# main.net
KiCad netlist of a schematic drawn in EAGLE
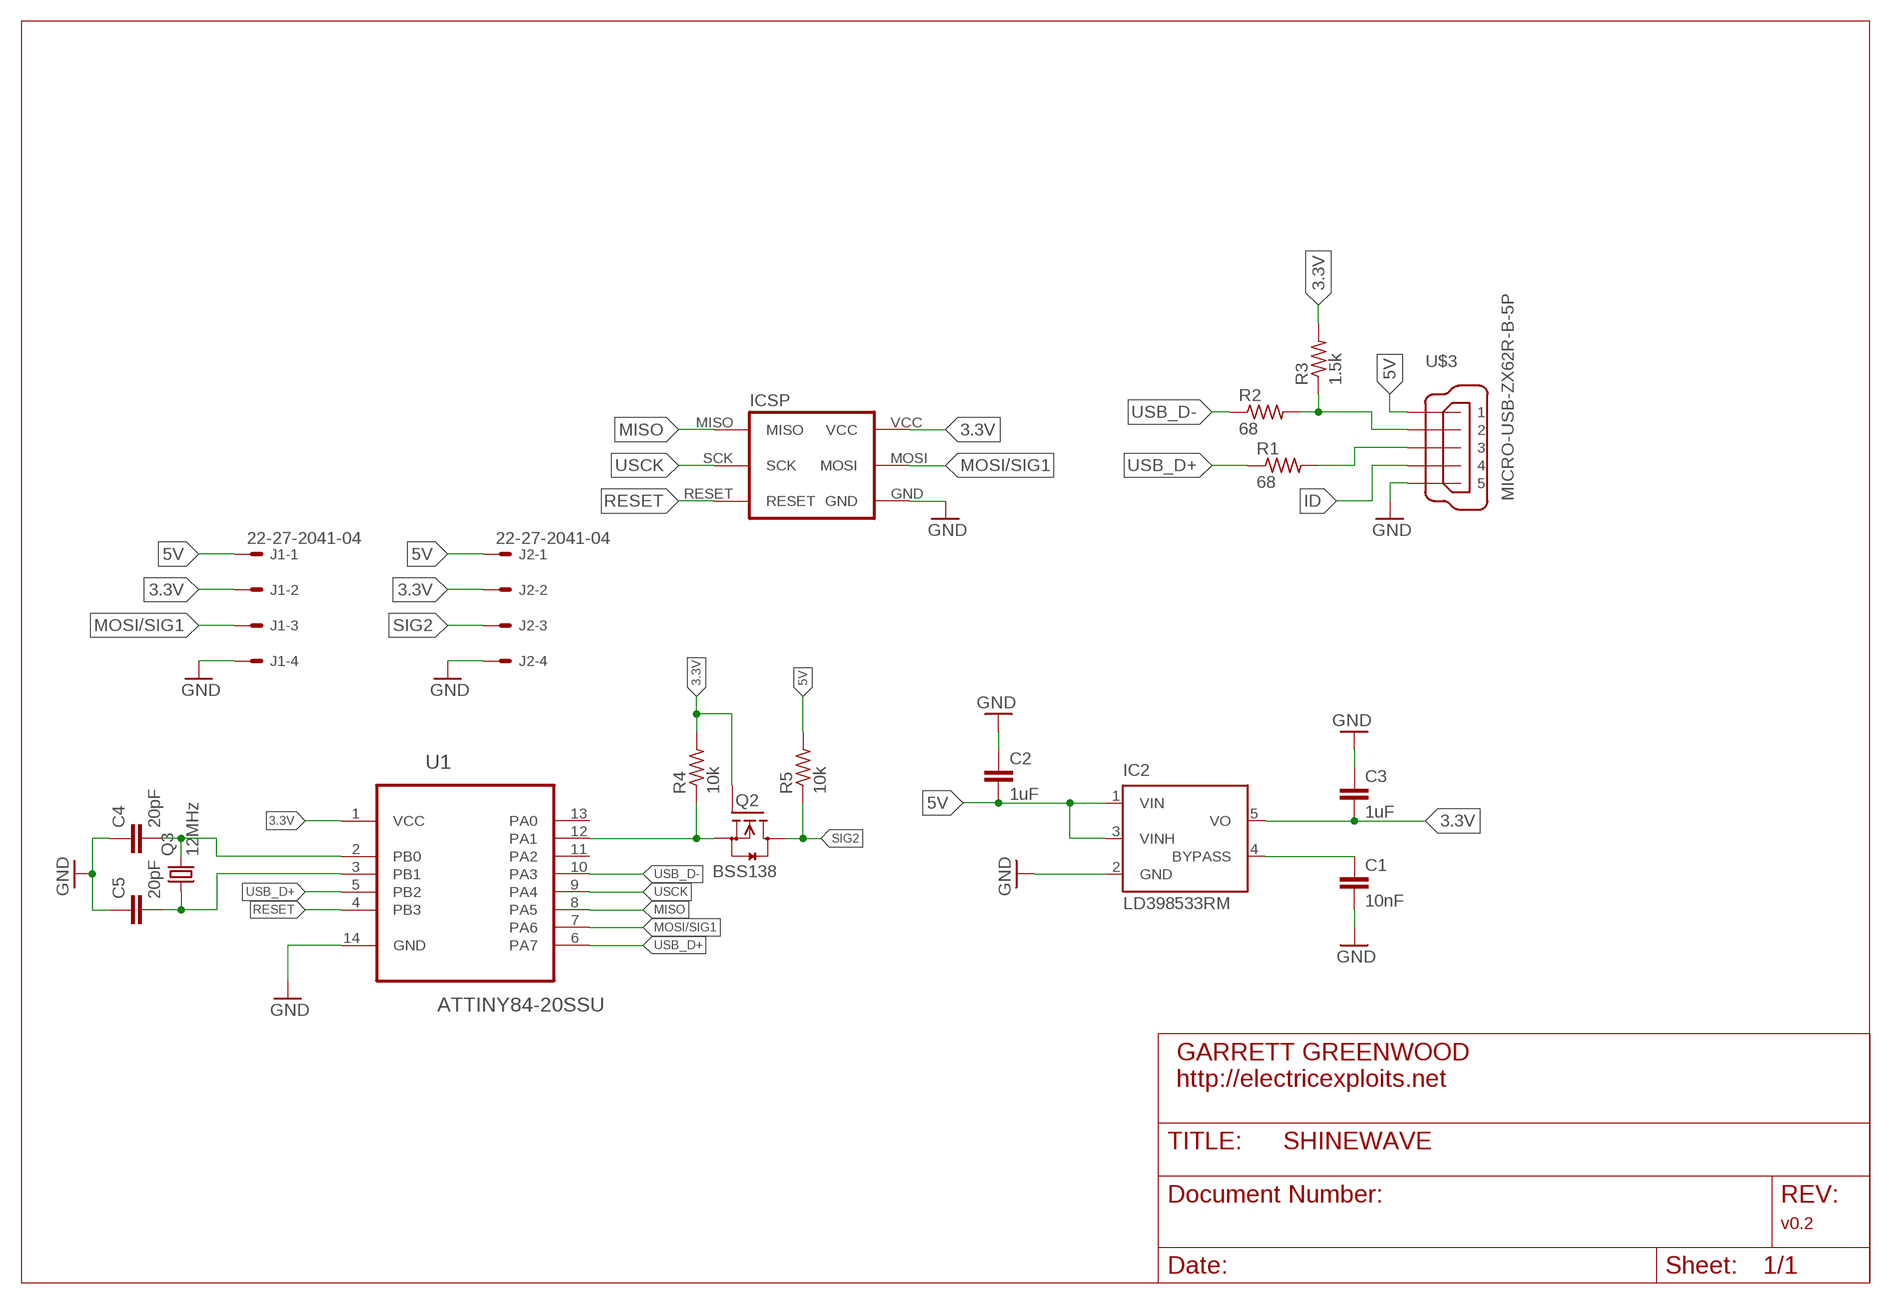
[diagram p0: schematic, sheet 1]

(export (version "E")
  (design (tool "Eeschema 10.0.6"))
  (components
    (comp (ref "C1")
      (value "10nF")
      (footprint "eagle-import:C0603")
      (libsource (lib "eagle-import") (part "C-EUC0603"))
    )
    (comp (ref "C2")
      (value "1uF")
      (footprint "eagle-import:C0603")
      (libsource (lib "eagle-import") (part "C-EUC0603"))
    )
    (comp (ref "C3")
      (value "1uF")
      (footprint "eagle-import:C0603")
      (libsource (lib "eagle-import") (part "C-EUC0603"))
    )
    (comp (ref "C4")
      (value "20pF")
      (footprint "eagle-import:C0603")
      (libsource (lib "eagle-import") (part "C-EUC0603"))
    )
    (comp (ref "C5")
      (value "20pF")
      (footprint "eagle-import:C0603")
      (libsource (lib "eagle-import") (part "C-EUC0603"))
    )
    (comp (ref "IC2")
      (value "LD398533RM")
      (footprint "eagle-import:SOT23-5L")
      (libsource (lib "eagle-import") (part "LD3985M33R"))
    )
    (comp (ref "J1")
      (value "22-27-2041-04")
      (footprint "eagle-import:6410-04")
      (libsource (lib "eagle-import") (part "22-?-0427-2041"))
    )
    (comp (ref "J2")
      (value "22-27-2041-04")
      (footprint "eagle-import:6410-04")
      (libsource (lib "eagle-import") (part "22-?-0427-2041"))
    )
    (comp (ref "Q2")
      (value "BSS138")
      (footprint "eagle-import:SOT23")
      (libsource (lib "eagle-import") (part "BSS138"))
    )
    (comp (ref "Q3")
      (value "12MHz")
      (footprint "eagle-import:CTS406")
      (libsource (lib "eagle-import") (part "CRYSTALCTS406"))
    )
    (comp (ref "R1")
      (value "68")
      (footprint "eagle-import:R0603")
      (libsource (lib "eagle-import") (part "R-US_R0603"))
    )
    (comp (ref "R2")
      (value "68")
      (footprint "eagle-import:R0603")
      (libsource (lib "eagle-import") (part "R-US_R0603"))
    )
    (comp (ref "R3")
      (value "1.5k")
      (footprint "eagle-import:R0603")
      (libsource (lib "eagle-import") (part "R-US_R0603"))
    )
    (comp (ref "R4")
      (value "10k")
      (footprint "eagle-import:R0603")
      (libsource (lib "eagle-import") (part "R-US_R0603"))
    )
    (comp (ref "R5")
      (value "10k")
      (footprint "eagle-import:R0603")
      (libsource (lib "eagle-import") (part "R-US_R0603"))
    )
    (comp (ref "U$1")
      (value "ICSP_POGO_INTERFACE")
      (footprint "eagle-import:ICSP_SMD")
      (libsource (lib "eagle-import") (part "ICSP_POGO_INTERFACE"))
    )
    (comp (ref "U$3")
      (value "MICRO-USB-ZX62R-B-5P")
      (footprint "eagle-import:ZX62R-B-5P")
      (libsource (lib "eagle-import") (part "MICRO-USB-ZX62R-B-5P"))
    )
    (comp (ref "U1")
      (value "ATTINY84-20SSU")
      (footprint "eagle-import:SOIC127P600X175-14N")
      (libsource (lib "eagle-import") (part "ATTINY84-20SSU"))
    )
  )
  (nets
    (net (code "1") (name "3.3V") (class "Default")
      (node (ref "C3") (pin "2") (pinfunction "2_2") (pintype "passive"))
      (node (ref "IC2") (pin "5") (pinfunction "VO_5") (pintype "output"))
      (node (ref "J1") (pin "2") (pinfunction "S_2") (pintype "passive"))
      (node (ref "J2") (pin "2") (pinfunction "S_2") (pintype "passive"))
      (node (ref "Q2") (pin "1") (pinfunction "G_1") (pintype "passive"))
      (node (ref "R3") (pin "2") (pinfunction "2_2") (pintype "passive"))
      (node (ref "R4") (pin "2") (pinfunction "2_2") (pintype "passive"))
      (node (ref "U$1") (pin "VCC") (pinfunction "VCC_VCC") (pintype "bidirectional"))
      (node (ref "U1") (pin "1") (pinfunction "VCC_1") (pintype "power_in"))
    )
    (net (code "2") (name "5V") (class "Default")
      (node (ref "C2") (pin "2") (pinfunction "2_2") (pintype "passive"))
      (node (ref "IC2") (pin "1") (pinfunction "VIN_1") (pintype "input"))
      (node (ref "IC2") (pin "3") (pinfunction "VINH_3") (pintype "input"))
      (node (ref "J1") (pin "1") (pinfunction "S_1") (pintype "passive"))
      (node (ref "J2") (pin "1") (pinfunction "S_1") (pintype "passive"))
      (node (ref "R5") (pin "2") (pinfunction "2_2") (pintype "passive"))
      (node (ref "U$3") (pin "1") (pinfunction "1_1") (pintype "input"))
    )
    (net (code "3") (name "GND") (class "Default")
      (node (ref "C1") (pin "2") (pinfunction "2_2") (pintype "passive"))
      (node (ref "C2") (pin "1") (pinfunction "1_1") (pintype "passive"))
      (node (ref "C3") (pin "1") (pinfunction "1_1") (pintype "passive"))
      (node (ref "C4") (pin "1") (pinfunction "1_1") (pintype "passive"))
      (node (ref "C5") (pin "1") (pinfunction "1_1") (pintype "passive"))
      (node (ref "IC2") (pin "2") (pinfunction "GND_2") (pintype "power_in"))
      (node (ref "J1") (pin "4") (pinfunction "S_4") (pintype "passive"))
      (node (ref "J2") (pin "4") (pinfunction "S_4") (pintype "passive"))
      (node (ref "U$1") (pin "GND") (pinfunction "GND_GND") (pintype "bidirectional"))
      (node (ref "U$3") (pin "5") (pinfunction "5_5") (pintype "input"))
      (node (ref "U1") (pin "14") (pinfunction "GND_14") (pintype "passive"))
    )
    (net (code "4") (name "ID") (class "Default")
      (node (ref "U$3") (pin "4") (pinfunction "4_4") (pintype "input"))
    )
    (net (code "5") (name "MISO") (class "Default")
      (node (ref "U$1") (pin "MISO") (pinfunction "MISO_MISO") (pintype "bidirectional"))
      (node (ref "U1") (pin "8") (pinfunction "PA5_8") (pintype "bidirectional"))
    )
    (net (code "6") (name "MOSI{slash}SIG1") (class "Default")
      (node (ref "J1") (pin "3") (pinfunction "S_3") (pintype "passive"))
      (node (ref "U$1") (pin "MOSI") (pinfunction "MOSI_MOSI") (pintype "bidirectional"))
      (node (ref "U1") (pin "7") (pinfunction "PA6_7") (pintype "bidirectional"))
    )
    (net (code "7") (name "Net-(IC2-BYPASS)") (class "Default")
      (node (ref "C1") (pin "1") (pinfunction "1_1") (pintype "passive"))
      (node (ref "IC2") (pin "4") (pinfunction "BYPASS_4") (pintype "passive"))
    )
    (net (code "8") (name "Net-(Q2-S)") (class "Default")
      (node (ref "Q2") (pin "2") (pinfunction "S_2") (pintype "passive"))
      (node (ref "R4") (pin "1") (pinfunction "1_1") (pintype "passive"))
      (node (ref "U1") (pin "12") (pinfunction "PA1_12") (pintype "bidirectional"))
    )
    (net (code "9") (name "Net-(Q3-2)") (class "Default")
      (node (ref "C4") (pin "2") (pinfunction "2_2") (pintype "passive"))
      (node (ref "Q3") (pin "3") (pinfunction "2_3") (pintype "passive"))
      (node (ref "U1") (pin "2") (pinfunction "PB0_2") (pintype "bidirectional"))
    )
    (net (code "10") (name "Net-(R1-Pad2)") (class "Default")
      (node (ref "R1") (pin "2") (pinfunction "2_2") (pintype "passive"))
      (node (ref "U$3") (pin "3") (pinfunction "3_3") (pintype "input"))
    )
    (net (code "11") (name "Net-(R2-Pad2)") (class "Default")
      (node (ref "R2") (pin "2") (pinfunction "2_2") (pintype "passive"))
      (node (ref "R3") (pin "1") (pinfunction "1_1") (pintype "passive"))
      (node (ref "U$3") (pin "2") (pinfunction "2_2") (pintype "input"))
    )
    (net (code "12") (name "Net-(U1-PB1)") (class "Default")
      (node (ref "C5") (pin "2") (pinfunction "2_2") (pintype "passive"))
      (node (ref "Q3") (pin "1") (pinfunction "1_1") (pintype "passive"))
      (node (ref "U1") (pin "3") (pinfunction "PB1_3") (pintype "bidirectional"))
    )
    (net (code "13") (name "RESET") (class "Default")
      (node (ref "U$1") (pin "RESET") (pinfunction "RESET_RESET") (pintype "bidirectional"))
      (node (ref "U1") (pin "4") (pinfunction "PB3_4") (pintype "bidirectional"))
    )
    (net (code "14") (name "SIG2") (class "Default")
      (node (ref "J2") (pin "3") (pinfunction "S_3") (pintype "passive"))
      (node (ref "Q2") (pin "3") (pinfunction "D_3") (pintype "passive"))
      (node (ref "R5") (pin "1") (pinfunction "1_1") (pintype "passive"))
    )
    (net (code "15") (name "USB_D+") (class "Default")
      (node (ref "R1") (pin "1") (pinfunction "1_1") (pintype "passive"))
      (node (ref "U1") (pin "5") (pinfunction "PB2_5") (pintype "bidirectional"))
      (node (ref "U1") (pin "6") (pinfunction "PA7_6") (pintype "bidirectional"))
    )
    (net (code "16") (name "USB_D-") (class "Default")
      (node (ref "R2") (pin "1") (pinfunction "1_1") (pintype "passive"))
      (node (ref "U1") (pin "10") (pinfunction "PA3_10") (pintype "bidirectional"))
    )
    (net (code "17") (name "USCK") (class "Default")
      (node (ref "U$1") (pin "SCK") (pinfunction "SCK_SCK") (pintype "bidirectional"))
      (node (ref "U1") (pin "9") (pinfunction "PA4_9") (pintype "bidirectional"))
    )
    (net (code "18") (name "unconnected-(U1-PA0-Pad13)") (class "Default")
      (node (ref "U1") (pin "13") (pinfunction "PA0_13") (pintype "bidirectional"))
    )
    (net (code "19") (name "unconnected-(U1-PA2-Pad11)") (class "Default")
      (node (ref "U1") (pin "11") (pinfunction "PA2_11") (pintype "bidirectional"))
    )
  )
)
